# dogeversity.net
KiCad netlist of a schematic drawn in EAGLE
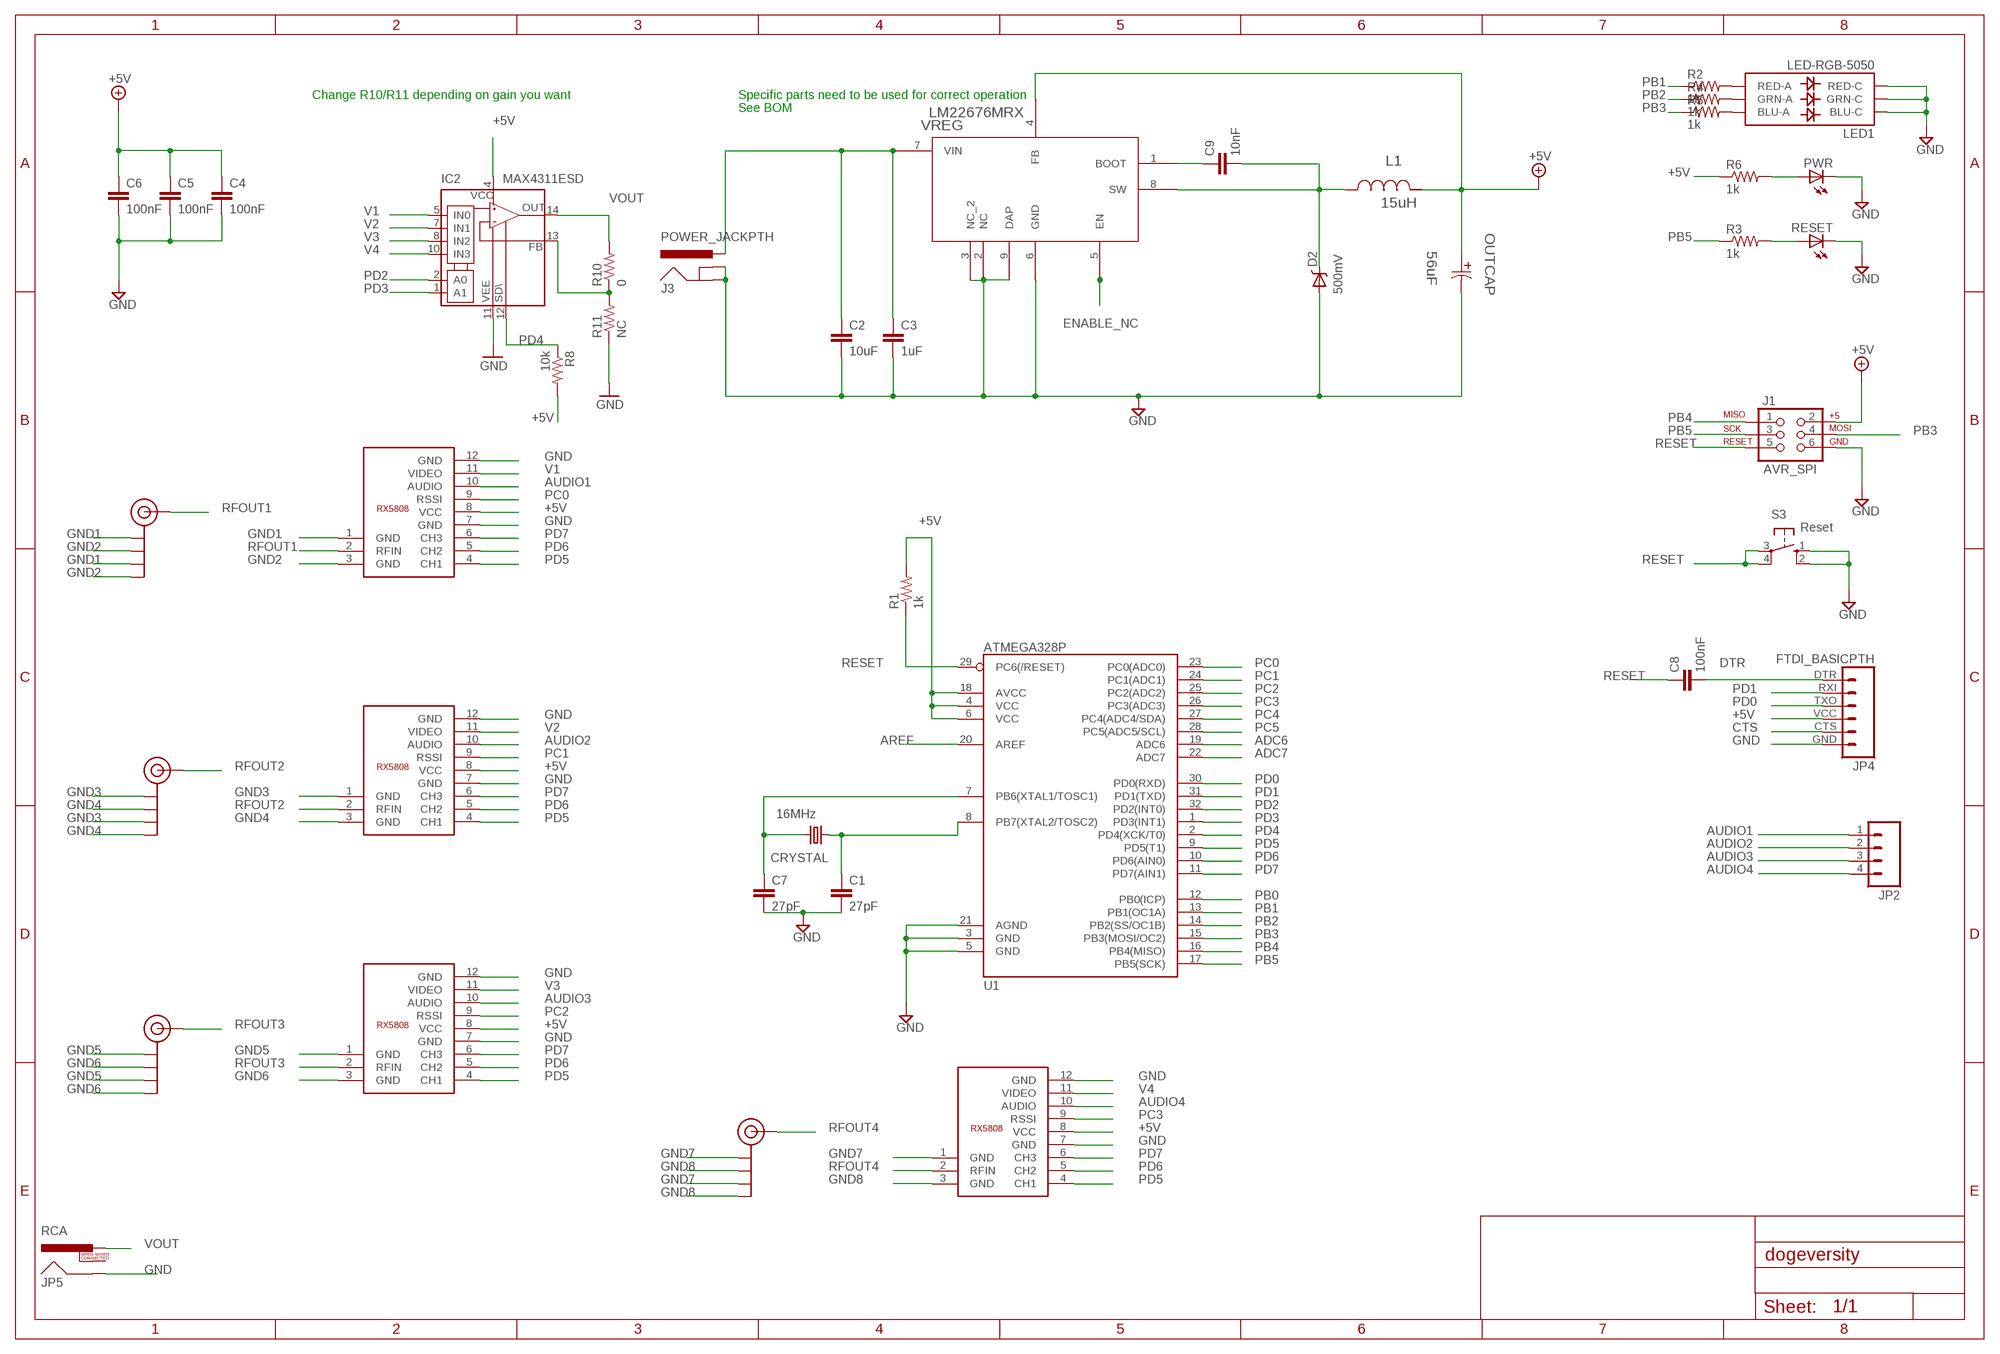
[diagram p0: schematic, sheet 1]

(export (version "E")
  (design (tool "Eeschema 10.0.6"))
  (components
    (comp (ref "C1")
      (value "27pF")
      (footprint "eagle-import:0603-CAP")
      (libsource (lib "eagle-import") (part "SparkFun-Passives_CAP0603-CAP"))
    )
    (comp (ref "C2")
      (value "10uF")
      (footprint "eagle-import:1206")
      (libsource (lib "eagle-import") (part "CAP1206"))
    )
    (comp (ref "C3")
      (value "1uF")
      (footprint "eagle-import:0603-CAP")
      (libsource (lib "eagle-import") (part "CAP0603-CAP"))
    )
    (comp (ref "C4")
      (value "100nF")
      (footprint "eagle-import:0603-CAP")
      (libsource (lib "eagle-import") (part "SparkFun-Passives_CAP0603-CAP"))
    )
    (comp (ref "C5")
      (value "100nF")
      (footprint "eagle-import:0603-CAP")
      (libsource (lib "eagle-import") (part "SparkFun-Passives_CAP0603-CAP"))
    )
    (comp (ref "C6")
      (value "100nF")
      (footprint "eagle-import:0603-CAP")
      (libsource (lib "eagle-import") (part "SparkFun-Passives_CAP0603-CAP"))
    )
    (comp (ref "C7")
      (value "27pF")
      (footprint "eagle-import:0603-CAP")
      (libsource (lib "eagle-import") (part "SparkFun-Passives_CAP0603-CAP"))
    )
    (comp (ref "C8")
      (value "100nF")
      (footprint "eagle-import:0603-CAP")
      (libsource (lib "eagle-import") (part "CAP0603-CAP"))
    )
    (comp (ref "C9")
      (value "10nF")
      (footprint "eagle-import:0805")
      (libsource (lib "eagle-import") (part "CAP0805"))
    )
    (comp (ref "CRYSTAL")
      (value "16MHz")
      (footprint "eagle-import:CRYSTAL-TXC-7A")
      (libsource (lib "eagle-import") (part "CRYSTALTXC-7A"))
    )
    (comp (ref "D2")
      (value "500mV")
      (footprint "eagle-import:SMA-DIODE")
      (libsource (lib "eagle-import") (part "DIODE-SCHOTTKY_"))
    )
    (comp (ref "IC2")
      (value "MAX4311ESD")
      (footprint "eagle-import:SO14")
      (fields (field (name "MF") "MAXIM") (field (name "MPN") "MAX4311ESD+"))
      (libsource (lib "eagle-import") (part "MAX4311ESD"))
    )
    (comp (ref "J$1")
      (value "SMA_EDGE")
      (footprint "eagle-import:SMA-EDGE")
      (libsource (lib "eagle-import") (part "SMA_EDGE"))
    )
    (comp (ref "J$2")
      (value "SMA_EDGE")
      (footprint "eagle-import:SMA-EDGE")
      (libsource (lib "eagle-import") (part "SMA_EDGE"))
    )
    (comp (ref "J$4")
      (value "SMA_EDGE")
      (footprint "eagle-import:SMA-EDGE")
      (libsource (lib "eagle-import") (part "SMA_EDGE"))
    )
    (comp (ref "J$5")
      (value "SMA_EDGE")
      (footprint "eagle-import:SMA-EDGE")
      (libsource (lib "eagle-import") (part "SMA_EDGE"))
    )
    (comp (ref "J1")
      (value "AVR_SPI")
      (footprint "eagle-import:2X3-NS")
      (libsource (lib "eagle-import") (part "AVR_SPI_PRG_6NS"))
    )
    (comp (ref "J3")
      (value "POWER_JACKPTH")
      (footprint "eagle-import:POWER_JACK_PTH")
      (libsource (lib "eagle-import") (part "POWER_JACKPTH"))
    )
    (comp (ref "JP2")
      (value "M04PTH")
      (footprint "eagle-import:1X04")
      (libsource (lib "eagle-import") (part "M04PTH"))
    )
    (comp (ref "JP4")
      (value "FTDI_BASICPTH")
      (footprint "eagle-import:FTDI_BASIC")
      (libsource (lib "eagle-import") (part "FTDI_BASICPTH"))
    )
    (comp (ref "JP5")
      (value "RCA")
      (footprint "eagle-import:RCA")
      (libsource (lib "eagle-import") (part "RCA"))
    )
    (comp (ref "L1")
      (value "15uH")
      (footprint "eagle-import:XAL5050")
      (fields (field (name "MANUFACTURER_PART_NUMBER") "XAL5050-153MEB"))
      (libsource (lib "eagle-import") (part "XAL5050-153MEB"))
    )
    (comp (ref "LED1")
      (value "LED-RGB-5050")
      (footprint "eagle-import:LED-TRICOLOR-5050")
      (libsource (lib "eagle-import") (part "LED-TRICOLOR-5050NO_IC"))
    )
    (comp (ref "OUTCAP")
      (value "56uF")
      (footprint "eagle-import:PCAP_SVP_B6")
      (libsource (lib "eagle-import") (part "20SVPF56MX"))
    )
    (comp (ref "PWR")
      (value "LED-YELLOW0603")
      (footprint "eagle-import:LED-0603")
      (libsource (lib "eagle-import") (part "LED-YELLOW0603"))
    )
    (comp (ref "R1")
      (value "1k")
      (footprint "eagle-import:0603-RES")
      (libsource (lib "eagle-import") (part "RESISTOR0603"))
    )
    (comp (ref "R2")
      (value "1k")
      (footprint "eagle-import:0603-RES")
      (libsource (lib "eagle-import") (part "RESISTOR0603"))
    )
    (comp (ref "R3")
      (value "1k")
      (footprint "eagle-import:0603-RES")
      (libsource (lib "eagle-import") (part "RESISTOR0603"))
    )
    (comp (ref "R4")
      (value "1k")
      (footprint "eagle-import:0603-RES")
      (libsource (lib "eagle-import") (part "RESISTOR0603"))
    )
    (comp (ref "R5")
      (value "1k")
      (footprint "eagle-import:0603-RES")
      (libsource (lib "eagle-import") (part "RESISTOR0603"))
    )
    (comp (ref "R6")
      (value "1k")
      (footprint "eagle-import:0603-RES")
      (libsource (lib "eagle-import") (part "RESISTOR0603"))
    )
    (comp (ref "R8")
      (value "10k")
      (footprint "eagle-import:0603-RES")
      (libsource (lib "eagle-import") (part "RESISTOR0603"))
    )
    (comp (ref "R10")
      (value "0")
      (footprint "eagle-import:0603-RES")
      (libsource (lib "eagle-import") (part "RESISTOR0603"))
    )
    (comp (ref "R11")
      (value "NC")
      (footprint "eagle-import:0603-RES")
      (libsource (lib "eagle-import") (part "RESISTOR0603"))
    )
    (comp (ref "RESET")
      (value "LED-YELLOW0603")
      (footprint "eagle-import:LED-0603")
      (libsource (lib "eagle-import") (part "LED-YELLOW0603"))
    )
    (comp (ref "S3")
      (value "Reset")
      (footprint "eagle-import:B3F-10XX")
      (fields (field (name "MPN") "B3F-1000"))
      (libsource (lib "eagle-import") (part "10-XX"))
    )
    (comp (ref "U1")
      (value "ATMEGA328P")
      (footprint "eagle-import:TQFP32-08")
      (libsource (lib "eagle-import") (part "ATMEGA328_SMT"))
    )
    (comp (ref "VREG")
      (value "LM22676MRX")
      (footprint "eagle-import:MRA08B")
      (libsource (lib "eagle-import") (part "LM22676MRX"))
    )
    (comp (ref "`1")
      (value "RX5808")
      (footprint "eagle-import:RX5808")
      (libsource (lib "eagle-import") (part "RX5808"))
    )
    (comp (ref "`2")
      (value "RX5808")
      (footprint "eagle-import:RX5808")
      (libsource (lib "eagle-import") (part "RX5808"))
    )
    (comp (ref "`3")
      (value "RX5808")
      (footprint "eagle-import:RX5808")
      (libsource (lib "eagle-import") (part "RX5808"))
    )
    (comp (ref "`4")
      (value "RX5808")
      (footprint "eagle-import:RX5808")
      (libsource (lib "eagle-import") (part "RX5808"))
    )
  )
  (nets
    (net (code "1") (name "+5V") (class "Default")
      (node (ref "C4") (pin "1") (pinfunction "1_1") (pintype "passive"))
      (node (ref "C5") (pin "1") (pinfunction "1_1") (pintype "passive"))
      (node (ref "C6") (pin "1") (pinfunction "1_1") (pintype "passive"))
      (node (ref "IC2") (pin "4") (pinfunction "V+_4") (pintype "power_in"))
      (node (ref "J1") (pin "2") (pinfunction "2_2") (pintype "passive"))
      (node (ref "JP4") (pin "VCC") (pinfunction "4_VCC") (pintype "passive"))
      (node (ref "L1") (pin "1") (pinfunction "1_1") (pintype "passive"))
      (node (ref "OUTCAP") (pin "1") (pinfunction "1_1") (pintype "passive"))
      (node (ref "R1") (pin "2") (pinfunction "2_2") (pintype "passive"))
      (node (ref "R6") (pin "1") (pinfunction "1_1") (pintype "passive"))
      (node (ref "R8") (pin "2") (pinfunction "2_2") (pintype "passive"))
      (node (ref "U1") (pin "18") (pinfunction "AVCC_18") (pintype "bidirectional"))
      (node (ref "U1") (pin "4") (pinfunction "VCC_4") (pintype "bidirectional"))
      (node (ref "U1") (pin "6") (pinfunction "VCC_6") (pintype "bidirectional"))
      (node (ref "VREG") (pin "4") (pinfunction "FB_4") (pintype "input"))
      (node (ref "`1") (pin "8") (pinfunction "VCC_8") (pintype "bidirectional"))
      (node (ref "`2") (pin "8") (pinfunction "VCC_8") (pintype "bidirectional"))
      (node (ref "`3") (pin "8") (pinfunction "VCC_8") (pintype "bidirectional"))
      (node (ref "`4") (pin "8") (pinfunction "VCC_8") (pintype "bidirectional"))
    )
    (net (code "2") (name "/ADC6") (class "Default")
      (node (ref "U1") (pin "19") (pinfunction "ADC6_19") (pintype "bidirectional"))
    )
    (net (code "3") (name "/ADC7") (class "Default")
      (node (ref "U1") (pin "22") (pinfunction "ADC7_22") (pintype "bidirectional"))
    )
    (net (code "4") (name "/AREF") (class "Default")
      (node (ref "U1") (pin "20") (pinfunction "AREF_20") (pintype "bidirectional"))
    )
    (net (code "5") (name "/AUDIO1") (class "Default")
      (node (ref "JP2") (pin "1") (pinfunction "1_1") (pintype "passive"))
      (node (ref "`1") (pin "10") (pinfunction "AUDIO_10") (pintype "bidirectional"))
    )
    (net (code "6") (name "/AUDIO2") (class "Default")
      (node (ref "JP2") (pin "2") (pinfunction "2_2") (pintype "passive"))
      (node (ref "`2") (pin "10") (pinfunction "AUDIO_10") (pintype "bidirectional"))
    )
    (net (code "7") (name "/AUDIO3") (class "Default")
      (node (ref "JP2") (pin "3") (pinfunction "3_3") (pintype "passive"))
      (node (ref "`3") (pin "10") (pinfunction "AUDIO_10") (pintype "bidirectional"))
    )
    (net (code "8") (name "/AUDIO4") (class "Default")
      (node (ref "JP2") (pin "4") (pinfunction "4_4") (pintype "passive"))
      (node (ref "`4") (pin "10") (pinfunction "AUDIO_10") (pintype "bidirectional"))
    )
    (net (code "9") (name "/CTS") (class "Default")
      (node (ref "JP4") (pin "CTS") (pinfunction "5_CTS") (pintype "passive"))
    )
    (net (code "10") (name "/DTR") (class "Default")
      (node (ref "C8") (pin "2") (pinfunction "2_2") (pintype "passive"))
      (node (ref "JP4") (pin "DTR") (pinfunction "1_DTR") (pintype "passive"))
    )
    (net (code "11") (name "/ENABLE_NC") (class "Default")
      (node (ref "VREG") (pin "5") (pinfunction "EN_5") (pintype "input"))
    )
    (net (code "12") (name "/GND1") (class "Default")
      (node (ref "J$1") (pin "GND@0") (pinfunction "GND_GND@0") (pintype "bidirectional"))
      (node (ref "J$1") (pin "GND@2") (pinfunction "GND_GND@2") (pintype "bidirectional"))
      (node (ref "`1") (pin "1") (pinfunction "GND_1") (pintype "bidirectional"))
    )
    (net (code "13") (name "/GND2") (class "Default")
      (node (ref "J$1") (pin "GND@1") (pinfunction "GND_GND@1") (pintype "bidirectional"))
      (node (ref "J$1") (pin "GND@3") (pinfunction "GND_GND@3") (pintype "bidirectional"))
      (node (ref "`1") (pin "3") (pinfunction "GND_3") (pintype "bidirectional"))
    )
    (net (code "14") (name "/GND3") (class "Default")
      (node (ref "J$4") (pin "GND@0") (pinfunction "GND_GND@0") (pintype "bidirectional"))
      (node (ref "J$4") (pin "GND@2") (pinfunction "GND_GND@2") (pintype "bidirectional"))
      (node (ref "`2") (pin "1") (pinfunction "GND_1") (pintype "bidirectional"))
    )
    (net (code "15") (name "/GND4") (class "Default")
      (node (ref "J$4") (pin "GND@1") (pinfunction "GND_GND@1") (pintype "bidirectional"))
      (node (ref "J$4") (pin "GND@3") (pinfunction "GND_GND@3") (pintype "bidirectional"))
      (node (ref "`2") (pin "3") (pinfunction "GND_3") (pintype "bidirectional"))
    )
    (net (code "16") (name "/GND5") (class "Default")
      (node (ref "J$5") (pin "GND@0") (pinfunction "GND_GND@0") (pintype "bidirectional"))
      (node (ref "J$5") (pin "GND@2") (pinfunction "GND_GND@2") (pintype "bidirectional"))
      (node (ref "`3") (pin "1") (pinfunction "GND_1") (pintype "bidirectional"))
    )
    (net (code "17") (name "/GND6") (class "Default")
      (node (ref "J$5") (pin "GND@1") (pinfunction "GND_GND@1") (pintype "bidirectional"))
      (node (ref "J$5") (pin "GND@3") (pinfunction "GND_GND@3") (pintype "bidirectional"))
      (node (ref "`3") (pin "3") (pinfunction "GND_3") (pintype "bidirectional"))
    )
    (net (code "18") (name "/GND7") (class "Default")
      (node (ref "J$2") (pin "GND@0") (pinfunction "GND_GND@0") (pintype "bidirectional"))
      (node (ref "J$2") (pin "GND@2") (pinfunction "GND_GND@2") (pintype "bidirectional"))
      (node (ref "`4") (pin "1") (pinfunction "GND_1") (pintype "bidirectional"))
    )
    (net (code "19") (name "/GND8") (class "Default")
      (node (ref "J$2") (pin "GND@1") (pinfunction "GND_GND@1") (pintype "bidirectional"))
      (node (ref "J$2") (pin "GND@3") (pinfunction "GND_GND@3") (pintype "bidirectional"))
      (node (ref "`4") (pin "3") (pinfunction "GND_3") (pintype "bidirectional"))
    )
    (net (code "20") (name "/PB0") (class "Default")
      (node (ref "U1") (pin "12") (pinfunction "PB0(ICP)_12") (pintype "bidirectional"))
    )
    (net (code "21") (name "/PB1") (class "Default")
      (node (ref "R2") (pin "1") (pinfunction "1_1") (pintype "passive"))
      (node (ref "U1") (pin "13") (pinfunction "PB1(OC1A)_13") (pintype "bidirectional"))
    )
    (net (code "22") (name "/PB2") (class "Default")
      (node (ref "R4") (pin "1") (pinfunction "1_1") (pintype "passive"))
      (node (ref "U1") (pin "14") (pinfunction "PB2(SS/OC1B)_14") (pintype "bidirectional"))
    )
    (net (code "23") (name "/PB3") (class "Default")
      (node (ref "J1") (pin "4") (pinfunction "4_4") (pintype "passive"))
      (node (ref "R5") (pin "1") (pinfunction "1_1") (pintype "passive"))
      (node (ref "U1") (pin "15") (pinfunction "PB3(MOSI/OC2)_15") (pintype "bidirectional"))
    )
    (net (code "24") (name "/PB4") (class "Default")
      (node (ref "J1") (pin "1") (pinfunction "1_1") (pintype "passive"))
      (node (ref "U1") (pin "16") (pinfunction "PB4(MISO)_16") (pintype "bidirectional"))
    )
    (net (code "25") (name "/PB5") (class "Default")
      (node (ref "J1") (pin "3") (pinfunction "3_3") (pintype "passive"))
      (node (ref "R3") (pin "1") (pinfunction "1_1") (pintype "passive"))
      (node (ref "U1") (pin "17") (pinfunction "PB5(SCK)_17") (pintype "bidirectional"))
    )
    (net (code "26") (name "/PC0") (class "Default")
      (node (ref "U1") (pin "23") (pinfunction "PC0(ADC0)_23") (pintype "bidirectional"))
      (node (ref "`1") (pin "9") (pinfunction "RSSI_9") (pintype "bidirectional"))
    )
    (net (code "27") (name "/PC1") (class "Default")
      (node (ref "U1") (pin "24") (pinfunction "PC1(ADC1)_24") (pintype "bidirectional"))
      (node (ref "`2") (pin "9") (pinfunction "RSSI_9") (pintype "bidirectional"))
    )
    (net (code "28") (name "/PC2") (class "Default")
      (node (ref "U1") (pin "25") (pinfunction "PC2(ADC2)_25") (pintype "bidirectional"))
      (node (ref "`3") (pin "9") (pinfunction "RSSI_9") (pintype "bidirectional"))
    )
    (net (code "29") (name "/PC3") (class "Default")
      (node (ref "U1") (pin "26") (pinfunction "PC3(ADC3)_26") (pintype "bidirectional"))
      (node (ref "`4") (pin "9") (pinfunction "RSSI_9") (pintype "bidirectional"))
    )
    (net (code "30") (name "/PC4") (class "Default")
      (node (ref "U1") (pin "27") (pinfunction "PC4(ADC4/SDA)_27") (pintype "bidirectional"))
    )
    (net (code "31") (name "/PC5") (class "Default")
      (node (ref "U1") (pin "28") (pinfunction "PC5(ADC5/SCL)_28") (pintype "bidirectional"))
    )
    (net (code "32") (name "/PD0") (class "Default")
      (node (ref "JP4") (pin "TXO") (pinfunction "3_TXO") (pintype "passive"))
      (node (ref "U1") (pin "30") (pinfunction "PD0(RXD)_30") (pintype "bidirectional"))
    )
    (net (code "33") (name "/PD1") (class "Default")
      (node (ref "JP4") (pin "RXI") (pinfunction "2_RXI") (pintype "passive"))
      (node (ref "U1") (pin "31") (pinfunction "PD1(TXD)_31") (pintype "bidirectional"))
    )
    (net (code "34") (name "/PD2") (class "Default")
      (node (ref "IC2") (pin "2") (pinfunction "A0_2") (pintype "input"))
      (node (ref "U1") (pin "32") (pinfunction "PD2(INT0)_32") (pintype "bidirectional"))
    )
    (net (code "35") (name "/PD3") (class "Default")
      (node (ref "IC2") (pin "1") (pinfunction "A1_1") (pintype "input"))
      (node (ref "U1") (pin "1") (pinfunction "PD3(INT1)_1") (pintype "bidirectional"))
    )
    (net (code "36") (name "/PD4") (class "Default")
      (node (ref "IC2") (pin "12") (pinfunction "~{SHDN}_12") (pintype "input"))
      (node (ref "R8") (pin "1") (pinfunction "1_1") (pintype "passive"))
      (node (ref "U1") (pin "2") (pinfunction "PD4(XCK/T0)_2") (pintype "bidirectional"))
    )
    (net (code "37") (name "/PD5") (class "Default")
      (node (ref "U1") (pin "9") (pinfunction "PD5(T1)_9") (pintype "bidirectional"))
      (node (ref "`1") (pin "4") (pinfunction "CH1_4") (pintype "bidirectional"))
      (node (ref "`2") (pin "4") (pinfunction "CH1_4") (pintype "bidirectional"))
      (node (ref "`3") (pin "4") (pinfunction "CH1_4") (pintype "bidirectional"))
      (node (ref "`4") (pin "4") (pinfunction "CH1_4") (pintype "bidirectional"))
    )
    (net (code "38") (name "/PD6") (class "Default")
      (node (ref "U1") (pin "10") (pinfunction "PD6(AIN0)_10") (pintype "bidirectional"))
      (node (ref "`1") (pin "5") (pinfunction "CH2_5") (pintype "bidirectional"))
      (node (ref "`2") (pin "5") (pinfunction "CH2_5") (pintype "bidirectional"))
      (node (ref "`3") (pin "5") (pinfunction "CH2_5") (pintype "bidirectional"))
      (node (ref "`4") (pin "5") (pinfunction "CH2_5") (pintype "bidirectional"))
    )
    (net (code "39") (name "/PD7") (class "Default")
      (node (ref "U1") (pin "11") (pinfunction "PD7(AIN1)_11") (pintype "bidirectional"))
      (node (ref "`1") (pin "6") (pinfunction "CH3_6") (pintype "bidirectional"))
      (node (ref "`2") (pin "6") (pinfunction "CH3_6") (pintype "bidirectional"))
      (node (ref "`3") (pin "6") (pinfunction "CH3_6") (pintype "bidirectional"))
      (node (ref "`4") (pin "6") (pinfunction "CH3_6") (pintype "bidirectional"))
    )
    (net (code "40") (name "/RESET") (class "Default")
      (node (ref "C8") (pin "1") (pinfunction "1_1") (pintype "passive"))
      (node (ref "J1") (pin "5") (pinfunction "5_5") (pintype "passive"))
      (node (ref "R1") (pin "1") (pinfunction "1_1") (pintype "passive"))
      (node (ref "S3") (pin "3") (pinfunction "P_3") (pintype "passive"))
      (node (ref "S3") (pin "4") (pinfunction "P1_4") (pintype "passive"))
      (node (ref "U1") (pin "29") (pinfunction "PC6(/RESET)_29") (pintype "bidirectional"))
    )
    (net (code "41") (name "/RFOUT1") (class "Default")
      (node (ref "J$1") (pin "SIG") (pinfunction "SIGNAL_SIG") (pintype "bidirectional"))
      (node (ref "`1") (pin "2") (pinfunction "RFIN_2") (pintype "bidirectional"))
    )
    (net (code "42") (name "/RFOUT2") (class "Default")
      (node (ref "J$4") (pin "SIG") (pinfunction "SIGNAL_SIG") (pintype "bidirectional"))
      (node (ref "`2") (pin "2") (pinfunction "RFIN_2") (pintype "bidirectional"))
    )
    (net (code "43") (name "/RFOUT3") (class "Default")
      (node (ref "J$5") (pin "SIG") (pinfunction "SIGNAL_SIG") (pintype "bidirectional"))
      (node (ref "`3") (pin "2") (pinfunction "RFIN_2") (pintype "bidirectional"))
    )
    (net (code "44") (name "/RFOUT4") (class "Default")
      (node (ref "J$2") (pin "SIG") (pinfunction "SIGNAL_SIG") (pintype "bidirectional"))
      (node (ref "`4") (pin "2") (pinfunction "RFIN_2") (pintype "bidirectional"))
    )
    (net (code "45") (name "/V1") (class "Default")
      (node (ref "IC2") (pin "5") (pinfunction "IN0_5") (pintype "input"))
      (node (ref "`1") (pin "11") (pinfunction "VIDEO_11") (pintype "bidirectional"))
    )
    (net (code "46") (name "/V2") (class "Default")
      (node (ref "IC2") (pin "7") (pinfunction "IN1_7") (pintype "input"))
      (node (ref "`2") (pin "11") (pinfunction "VIDEO_11") (pintype "bidirectional"))
    )
    (net (code "47") (name "/V3") (class "Default")
      (node (ref "IC2") (pin "8") (pinfunction "IN2_8") (pintype "input"))
      (node (ref "`3") (pin "11") (pinfunction "VIDEO_11") (pintype "bidirectional"))
    )
    (net (code "48") (name "/V4") (class "Default")
      (node (ref "IC2") (pin "10") (pinfunction "IN3_10") (pintype "input"))
      (node (ref "`4") (pin "11") (pinfunction "VIDEO_11") (pintype "bidirectional"))
    )
    (net (code "49") (name "/VOUT") (class "Default")
      (node (ref "IC2") (pin "14") (pinfunction "OUT_14") (pintype "output"))
      (node (ref "JP5") (pin "PIN") (pinfunction "PIN_PIN") (pintype "bidirectional"))
      (node (ref "R10") (pin "2") (pinfunction "2_2") (pintype "passive"))
    )
    (net (code "50") (name "GND") (class "Default")
      (node (ref "C1") (pin "2") (pinfunction "2_2") (pintype "passive"))
      (node (ref "C2") (pin "2") (pinfunction "2_2") (pintype "passive"))
      (node (ref "C3") (pin "2") (pinfunction "2_2") (pintype "passive"))
      (node (ref "C4") (pin "2") (pinfunction "2_2") (pintype "passive"))
      (node (ref "C5") (pin "2") (pinfunction "2_2") (pintype "passive"))
      (node (ref "C6") (pin "2") (pinfunction "2_2") (pintype "passive"))
      (node (ref "C7") (pin "2") (pinfunction "2_2") (pintype "passive"))
      (node (ref "D2") (pin "A") (pinfunction "A_A") (pintype "passive"))
      (node (ref "IC2") (pin "11") (pinfunction "V-_11") (pintype "power_in"))
      (node (ref "J1") (pin "6") (pinfunction "6_6") (pintype "passive"))
      (node (ref "J3") (pin "GND") (pinfunction "GND_GND") (pintype "bidirectional"))
      (node (ref "J3") (pin "GNDBREAK") (pinfunction "GNDBREAK_GNDBREAK") (pintype "bidirectional"))
      (node (ref "JP4") (pin "GND") (pinfunction "6_GND") (pintype "passive"))
      (node (ref "JP5") (pin "SHELL") (pinfunction "SHELL_SHELL") (pintype "bidirectional"))
      (node (ref "LED1") (pin "4") (pinfunction "BLU-C_4") (pintype "bidirectional"))
      (node (ref "LED1") (pin "5") (pinfunction "RED-C_5") (pintype "bidirectional"))
      (node (ref "LED1") (pin "6") (pinfunction "GRN-C_6") (pintype "bidirectional"))
      (node (ref "OUTCAP") (pin "2") (pinfunction "2_2") (pintype "passive"))
      (node (ref "PWR") (pin "C") (pinfunction "C_C") (pintype "passive"))
      (node (ref "R11") (pin "1") (pinfunction "1_1") (pintype "passive"))
      (node (ref "RESET") (pin "C") (pinfunction "C_C") (pintype "passive"))
      (node (ref "S3") (pin "1") (pinfunction "S_1") (pintype "passive"))
      (node (ref "S3") (pin "2") (pinfunction "S1_2") (pintype "passive"))
      (node (ref "U1") (pin "21") (pinfunction "AGND_21") (pintype "bidirectional"))
      (node (ref "U1") (pin "3") (pinfunction "GND_3") (pintype "bidirectional"))
      (node (ref "U1") (pin "5") (pinfunction "GND_5") (pintype "bidirectional"))
      (node (ref "VREG") (pin "2") (pinfunction "NC_2") (pintype "passive"))
      (node (ref "VREG") (pin "3") (pinfunction "NC_2_3") (pintype "passive"))
      (node (ref "VREG") (pin "6") (pinfunction "GND_6") (pintype "power_in"))
      (node (ref "VREG") (pin "9") (pinfunction "DAP_9") (pintype "power_in"))
      (node (ref "`1") (pin "12") (pinfunction "GND_12") (pintype "bidirectional"))
      (node (ref "`1") (pin "7") (pinfunction "GND_7") (pintype "bidirectional"))
      (node (ref "`2") (pin "12") (pinfunction "GND_12") (pintype "bidirectional"))
      (node (ref "`2") (pin "7") (pinfunction "GND_7") (pintype "bidirectional"))
      (node (ref "`3") (pin "12") (pinfunction "GND_12") (pintype "bidirectional"))
      (node (ref "`3") (pin "7") (pinfunction "GND_7") (pintype "bidirectional"))
      (node (ref "`4") (pin "12") (pinfunction "GND_12") (pintype "bidirectional"))
      (node (ref "`4") (pin "7") (pinfunction "GND_7") (pintype "bidirectional"))
    )
    (net (code "51") (name "Net-(CRYSTAL-1)") (class "Default")
      (node (ref "C1") (pin "1") (pinfunction "1_1") (pintype "passive"))
      (node (ref "CRYSTAL") (pin "P$1") (pinfunction "1_P$1") (pintype "passive"))
      (node (ref "U1") (pin "8") (pinfunction "PB7(XTAL2/TOSC2)_8") (pintype "bidirectional"))
    )
    (net (code "52") (name "Net-(CRYSTAL-2)") (class "Default")
      (node (ref "C7") (pin "1") (pinfunction "1_1") (pintype "passive"))
      (node (ref "CRYSTAL") (pin "P$2") (pinfunction "2_P$2") (pintype "passive"))
      (node (ref "U1") (pin "7") (pinfunction "PB6(XTAL1/TOSC1)_7") (pintype "bidirectional"))
    )
    (net (code "53") (name "Net-(IC2-FB)") (class "Default")
      (node (ref "IC2") (pin "13") (pinfunction "FB_13") (pintype "power_in"))
      (node (ref "R10") (pin "1") (pinfunction "1_1") (pintype "passive"))
      (node (ref "R11") (pin "2") (pinfunction "2_2") (pintype "passive"))
    )
    (net (code "54") (name "Net-(LED1-BLU-A)") (class "Default")
      (node (ref "LED1") (pin "3") (pinfunction "BLU-A_3") (pintype "bidirectional"))
      (node (ref "R5") (pin "2") (pinfunction "2_2") (pintype "passive"))
    )
    (net (code "55") (name "Net-(LED1-GRN-A)") (class "Default")
      (node (ref "LED1") (pin "1") (pinfunction "GRN-A_1") (pintype "bidirectional"))
      (node (ref "R4") (pin "2") (pinfunction "2_2") (pintype "passive"))
    )
    (net (code "56") (name "Net-(LED1-RED-A)") (class "Default")
      (node (ref "LED1") (pin "2") (pinfunction "RED-A_2") (pintype "bidirectional"))
      (node (ref "R2") (pin "2") (pinfunction "2_2") (pintype "passive"))
    )
    (net (code "57") (name "Net-(PWR-PadA)") (class "Default")
      (node (ref "PWR") (pin "A") (pinfunction "A_A") (pintype "passive"))
      (node (ref "R6") (pin "2") (pinfunction "2_2") (pintype "passive"))
    )
    (net (code "58") (name "Net-(R3-Pad2)") (class "Default")
      (node (ref "R3") (pin "2") (pinfunction "2_2") (pintype "passive"))
      (node (ref "RESET") (pin "A") (pinfunction "A_A") (pintype "passive"))
    )
    (net (code "59") (name "Net-(VREG-BOOT)") (class "Default")
      (node (ref "C9") (pin "1") (pinfunction "1_1") (pintype "passive"))
      (node (ref "VREG") (pin "1") (pinfunction "BOOT_1") (pintype "passive"))
    )
    (net (code "60") (name "Net-(VREG-SW)") (class "Default")
      (node (ref "C9") (pin "2") (pinfunction "2_2") (pintype "passive"))
      (node (ref "D2") (pin "C") (pinfunction "C_C") (pintype "passive"))
      (node (ref "L1") (pin "2") (pinfunction "2_2") (pintype "passive"))
      (node (ref "VREG") (pin "8") (pinfunction "SW_8") (pintype "power_in"))
    )
    (net (code "61") (name "Net-(VREG-VIN)") (class "Default")
      (node (ref "C2") (pin "1") (pinfunction "1_1") (pintype "passive"))
      (node (ref "C3") (pin "1") (pinfunction "1_1") (pintype "passive"))
      (node (ref "J3") (pin "PWR") (pinfunction "PWR_PWR") (pintype "bidirectional"))
      (node (ref "VREG") (pin "7") (pinfunction "VIN_7") (pintype "power_in"))
    )
    (net (code "62") (name "unconnected-(JP5-PadSWITCH)") (class "Default")
      (node (ref "JP5") (pin "SWITCH") (pinfunction "SWITCH_SWITCH") (pintype "bidirectional"))
    )
  )
)
